# 08_C8051_TIMER_LCD_V1_0_0.net
KiCad netlist of a schematic drawn in Altium Designer
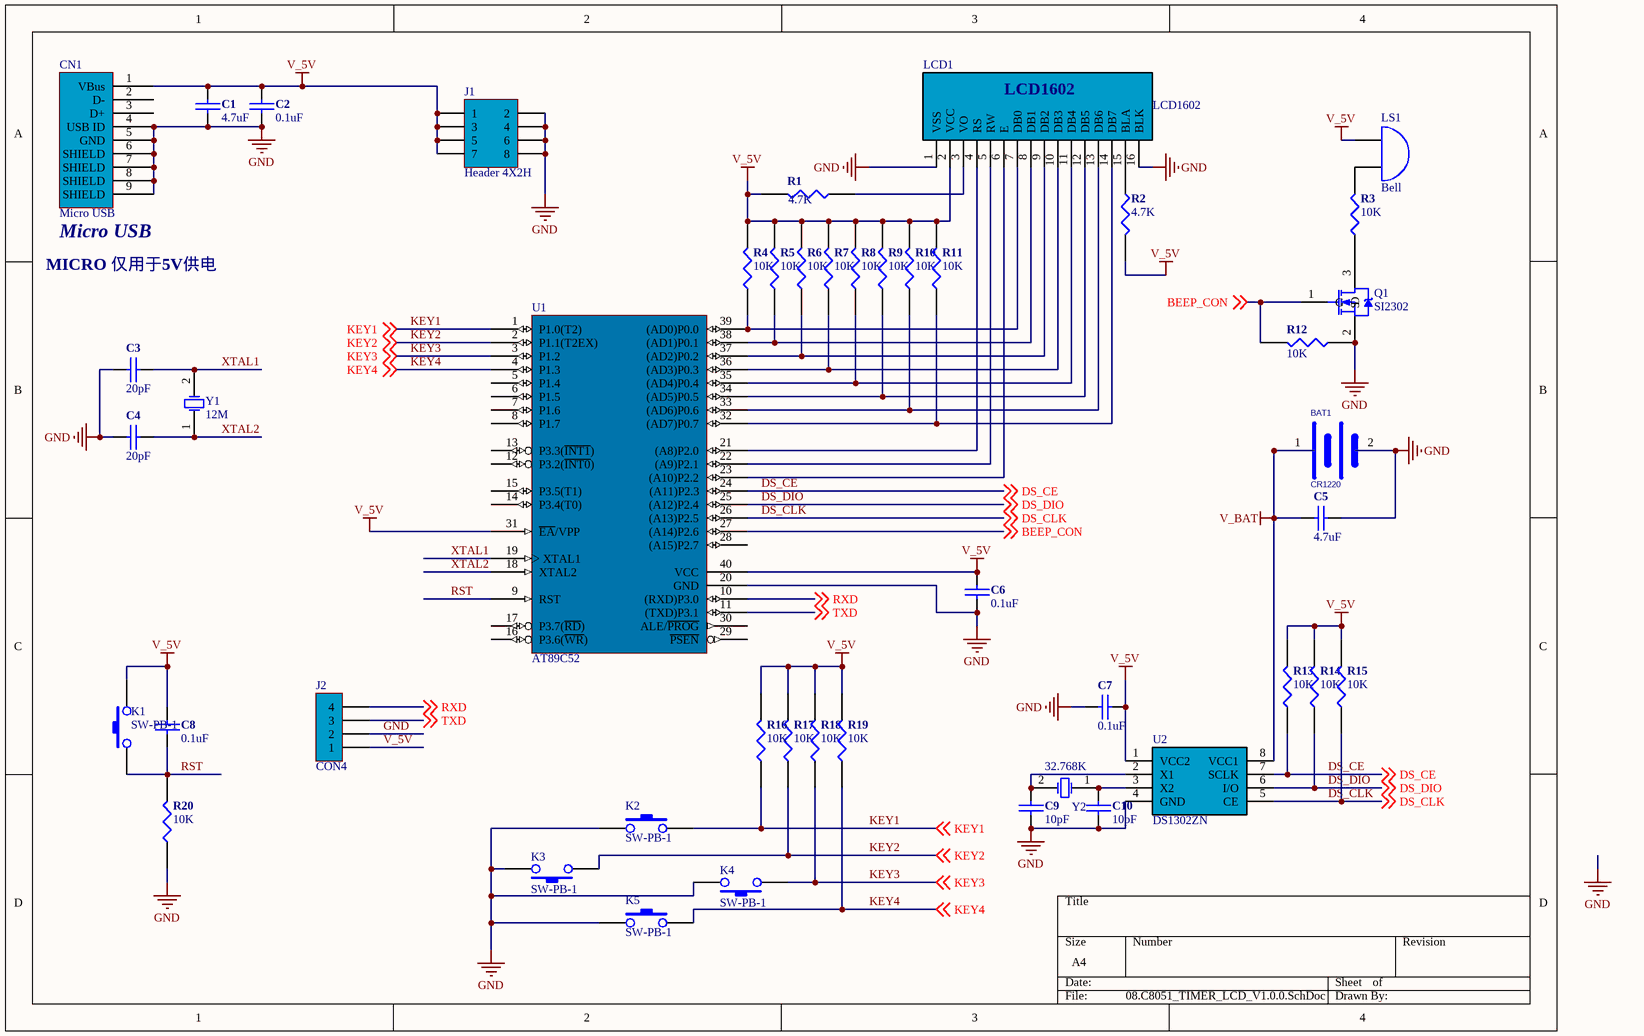
[diagram p0: 08.C8051_TIMER_LCD_V1.0.0.SchDoc]

(export (version "E")
  (design (tool "Eeschema 10.0.6"))
  (components
    (comp (ref "BAT1")
      (value "CR1220")
      (footprint "BATTERY-CELL")
      (libsource (lib "MyLibrarySum") (part "BATTERY"))
    )
    (comp (ref "C1")
      (value "4.7uF")
      (footprint "C0603")
      (description "SMT电容")
      (libsource (lib "") (part "CAP_1"))
    )
    (comp (ref "C2")
      (value "0.1uF")
      (footprint "C0603")
      (description "SMT电容")
      (libsource (lib "*") (part "电容"))
    )
    (comp (ref "C3")
      (value "20pF")
      (footprint "C0603")
      (description "SMT电容")
      (libsource (lib "*") (part "CAP"))
    )
    (comp (ref "C4")
      (value "20pF")
      (footprint "C0603")
      (description "SMT电容")
      (libsource (lib "*") (part "CAP"))
    )
    (comp (ref "C5")
      (value "4.7uF")
      (footprint "C0603")
      (description "SMT电容")
      (libsource (lib "*") (part "CAP"))
    )
    (comp (ref "C6")
      (value "0.1uF")
      (footprint "C0603")
      (description "SMT电容")
      (libsource (lib "*") (part "电容"))
    )
    (comp (ref "C7")
      (value "0.1uF")
      (footprint "C0603")
      (description "SMT电容")
      (libsource (lib "*") (part "电容"))
    )
    (comp (ref "C8")
      (value "0.1uF")
      (footprint "C0603")
      (description "SMT电容")
      (libsource (lib "*") (part "电容"))
    )
    (comp (ref "C9")
      (value "10pF")
      (footprint "C0603")
      (description "SMT电容")
      (libsource (lib "") (part "CAP_1"))
    )
    (comp (ref "C10")
      (value "10pF")
      (footprint "C0603")
      (description "SMT电容")
      (libsource (lib "") (part "CAP_1"))
    )
    (comp (ref "CN1")
      (value "Micro USB")
      (footprint "MICRO_USB_9")
      (description "Micro USB头")
      (fields (field (name "USAGE") "Micro USB"))
      (libsource (lib "MyLibrarySum") (part "Mini_USB_3"))
    )
    (comp (ref "J1")
      (value "Header 4X2H")
      (footprint "HDR2X4")
      (description "Header, 4-Pin, Dual row, Right Angle")
      (fields (field (name "PUBLISHER") "Altium Limited"))
      (libsource (lib "MyLibrarySum") (part "Header 4X2H"))
    )
    (comp (ref "J2")
      (value "CON4")
      (footprint "HDR1X4")
      (description "Connector")
      (libsource (lib "MyLibrarySum") (part "CON4"))
    )
    (comp (ref "K1")
      (value "SW-PB-1")
      (footprint "SWITCH_1")
      (description "轻触按键")
      (libsource (lib "HDZBLIB") (part "SW-PB-1"))
    )
    (comp (ref "K2")
      (value "SW-PB-1")
      (footprint "SWITCH_1")
      (description "轻触按键")
      (libsource (lib "HDZBLIB") (part "SW-PB-1"))
    )
    (comp (ref "K3")
      (value "SW-PB-1")
      (footprint "SWITCH_1")
      (description "轻触按键")
      (libsource (lib "HDZBLIB") (part "SW-PB-1"))
    )
    (comp (ref "K4")
      (value "SW-PB-1")
      (footprint "SWITCH_1")
      (description "轻触按键")
      (libsource (lib "HDZBLIB") (part "SW-PB-1"))
    )
    (comp (ref "K5")
      (value "SW-PB-1")
      (footprint "SWITCH_1")
      (description "轻触按键")
      (libsource (lib "HDZBLIB") (part "SW-PB-1"))
    )
    (comp (ref "LCD1")
      (value "LCD1602")
      (footprint "LCD1602")
      (libsource (lib "MyLibrarySum") (part "LCD1602"))
    )
    (comp (ref "LS1")
      (value "Bell")
      (footprint "BUZZER")
      (description "Electrical Bell")
      (fields (field (name "PUBLISHER") "Altium Limited"))
      (libsource (lib "MyLibrarySum") (part "Bell"))
    )
    (comp (ref "Q1")
      (value "SI2302")
      (footprint "SOT_23(N)")
      (description "N-Channel Power MOSFET")
      (fields (field (name "PUBLISHER") "Altium Limited"))
      (libsource (lib "MyLibrarySum") (part "NMOS-2"))
    )
    (comp (ref "R1")
      (value "4.7K")
      (footprint "R0603")
      (description "SMT电阻")
      (libsource (lib "*") (part "RES1"))
    )
    (comp (ref "R2")
      (value "4.7K")
      (footprint "R0603")
      (description "SMT电阻")
      (libsource (lib "*") (part "RES1"))
    )
    (comp (ref "R3")
      (value "10K")
      (footprint "R0603")
      (description "SMT电阻")
      (libsource (lib "*") (part "RES1"))
    )
    (comp (ref "R4")
      (value "10K")
      (footprint "R0603")
      (description "SMT电阻")
      (libsource (lib "*") (part "RES1"))
    )
    (comp (ref "R5")
      (value "10K")
      (footprint "R0603")
      (description "SMT电阻")
      (libsource (lib "*") (part "RES1"))
    )
    (comp (ref "R6")
      (value "10K")
      (footprint "R0603")
      (description "SMT电阻")
      (libsource (lib "*") (part "RES1"))
    )
    (comp (ref "R7")
      (value "10K")
      (footprint "R0603")
      (description "SMT电阻")
      (libsource (lib "*") (part "RES1"))
    )
    (comp (ref "R8")
      (value "10K")
      (footprint "R0603")
      (description "SMT电阻")
      (libsource (lib "*") (part "RES1"))
    )
    (comp (ref "R9")
      (value "10K")
      (footprint "R0603")
      (description "SMT电阻")
      (libsource (lib "*") (part "RES1"))
    )
    (comp (ref "R10")
      (value "10K")
      (footprint "R0603")
      (description "SMT电阻")
      (libsource (lib "*") (part "RES1"))
    )
    (comp (ref "R11")
      (value "10K")
      (footprint "R0603")
      (description "SMT电阻")
      (libsource (lib "*") (part "RES1"))
    )
    (comp (ref "R12")
      (value "10K")
      (footprint "R0603")
      (description "SMT电阻")
      (libsource (lib "*") (part "RES1"))
    )
    (comp (ref "R13")
      (value "10K")
      (footprint "R0603")
      (description "SMT电阻")
      (libsource (lib "*") (part "RES1"))
    )
    (comp (ref "R14")
      (value "10K")
      (footprint "R0603")
      (description "SMT电阻")
      (libsource (lib "*") (part "RES1"))
    )
    (comp (ref "R15")
      (value "10K")
      (footprint "R0603")
      (description "SMT电阻")
      (libsource (lib "*") (part "RES1"))
    )
    (comp (ref "R16")
      (value "10K")
      (footprint "R0603")
      (description "SMT电阻")
      (libsource (lib "*") (part "RES1"))
    )
    (comp (ref "R17")
      (value "10K")
      (footprint "R0603")
      (description "SMT电阻")
      (libsource (lib "*") (part "RES1"))
    )
    (comp (ref "R18")
      (value "10K")
      (footprint "R0603")
      (description "SMT电阻")
      (libsource (lib "*") (part "RES1"))
    )
    (comp (ref "R19")
      (value "10K")
      (footprint "R0603")
      (description "SMT电阻")
      (libsource (lib "*") (part "RES1"))
    )
    (comp (ref "R20")
      (value "10K")
      (footprint "R0603")
      (description "SMT电阻")
      (libsource (lib "*") (part "RES1"))
    )
    (comp (ref "U1")
      (value "AT89C52")
      (footprint "DIP40")
      (description "8-Bit Microcontroller with 8K Flash ROM")
      (libsource (lib "MyLibrarySum") (part "AT89C52"))
    )
    (comp (ref "U2") (value "DS1302ZN") (footprint "SOP-8") (libsource (lib "MyLibrarySum") (part "DS1302")))
    (comp (ref "Y1")
      (value "12M")
      (footprint "XTAL")
      (description "Crystal Oscillator")
      (fields (field (name "PUBLISHER") "Altium Limited"))
      (libsource (lib "MyLibrarySum") (part "XTAL"))
    )
    (comp (ref "Y2")
      (value "32.768K")
      (footprint "XTAL_32.768KHz")
      (description "Crystal Oscillator")
      (fields (field (name "PUBLISHER") "Altium Limited"))
      (libsource (lib "MyLibrarySum") (part "XTAL"))
    )
  )
  (nets
    (net (code "1") (name "/RST") (class "Default")
      (node (ref "C8") (pin "2") (pintype "passive"))
      (node (ref "K1") (pin "1") (pinfunction "1_1") (pintype "passive"))
      (node (ref "R20") (pin "2") (pinfunction "2_2") (pintype "passive"))
      (node (ref "U1") (pin "9") (pinfunction "RST_9") (pintype "input"))
    )
    (net (code "2") (name "/XTAL1") (class "Default")
      (node (ref "C3") (pin "1") (pinfunction "1_1") (pintype "passive"))
      (node (ref "U1") (pin "19") (pinfunction "XTAL1_19") (pintype "input"))
      (node (ref "Y1") (pin "2") (pinfunction "OSC2_2") (pintype "passive"))
    )
    (net (code "3") (name "/XTAL2") (class "Default")
      (node (ref "C4") (pin "1") (pinfunction "1_1") (pintype "passive"))
      (node (ref "U1") (pin "18") (pinfunction "XTAL2_18") (pintype "input"))
      (node (ref "Y1") (pin "1") (pinfunction "OSC1_1") (pintype "passive"))
    )
    (net (code "4") (name "BEEP_CON") (class "Default")
      (node (ref "Q1") (pin "1") (pinfunction "G_1") (pintype "passive"))
      (node (ref "R12") (pin "2") (pinfunction "2_2") (pintype "passive"))
      (node (ref "U1") (pin "27") (pinfunction "(A14)P2.6_27") (pintype "bidirectional"))
    )
    (net (code "5") (name "DS_CE") (class "Default")
      (node (ref "R13") (pin "1") (pinfunction "1_1") (pintype "passive"))
      (node (ref "U1") (pin "24") (pinfunction "(A11)P2.3_24") (pintype "bidirectional"))
      (node (ref "U2") (pin "7") (pinfunction "SCLK_7") (pintype "passive"))
    )
    (net (code "6") (name "DS_CLK") (class "Default")
      (node (ref "R15") (pin "1") (pinfunction "1_1") (pintype "passive"))
      (node (ref "U1") (pin "26") (pinfunction "(A13)P2.5_26") (pintype "bidirectional"))
      (node (ref "U2") (pin "5") (pinfunction "CE_5") (pintype "passive"))
    )
    (net (code "7") (name "DS_DIO") (class "Default")
      (node (ref "R14") (pin "1") (pinfunction "1_1") (pintype "passive"))
      (node (ref "U1") (pin "25") (pinfunction "(A12)P2.4_25") (pintype "bidirectional"))
      (node (ref "U2") (pin "6") (pinfunction "I/O_6") (pintype "passive"))
    )
    (net (code "8") (name "GND") (class "Default")
      (node (ref "BAT1") (pin "2") (pinfunction "GND_2") (pintype "passive"))
      (node (ref "C1") (pin "1") (pinfunction "1_1") (pintype "passive"))
      (node (ref "C10") (pin "2") (pinfunction "2_2") (pintype "passive"))
      (node (ref "C2") (pin "2") (pintype "passive"))
      (node (ref "C3") (pin "2") (pinfunction "2_2") (pintype "passive"))
      (node (ref "C4") (pin "2") (pinfunction "2_2") (pintype "passive"))
      (node (ref "C5") (pin "1") (pinfunction "1_1") (pintype "passive"))
      (node (ref "C6") (pin "2") (pintype "passive"))
      (node (ref "C7") (pin "1") (pintype "passive"))
      (node (ref "C9") (pin "2") (pinfunction "2_2") (pintype "passive"))
      (node (ref "CN1") (pin "4") (pinfunction "USB_ID_4") (pintype "passive"))
      (node (ref "CN1") (pin "5") (pinfunction "GND_5") (pintype "passive"))
      (node (ref "CN1") (pin "6") (pinfunction "SHIELD_6") (pintype "passive"))
      (node (ref "CN1") (pin "7") (pinfunction "SHIELD_7") (pintype "passive"))
      (node (ref "CN1") (pin "8") (pinfunction "SHIELD_8") (pintype "passive"))
      (node (ref "CN1") (pin "9") (pinfunction "SHIELD_9") (pintype "passive"))
      (node (ref "J1") (pin "2") (pinfunction "2_2") (pintype "passive"))
      (node (ref "J1") (pin "4") (pinfunction "4_4") (pintype "passive"))
      (node (ref "J1") (pin "6") (pinfunction "6_6") (pintype "passive"))
      (node (ref "J1") (pin "8") (pinfunction "8_8") (pintype "passive"))
      (node (ref "J2") (pin "2") (pinfunction "2_2") (pintype "passive"))
      (node (ref "K2") (pin "1") (pinfunction "1_1") (pintype "passive"))
      (node (ref "K3") (pin "2") (pinfunction "2_2") (pintype "passive"))
      (node (ref "K4") (pin "2") (pinfunction "2_2") (pintype "passive"))
      (node (ref "K5") (pin "1") (pinfunction "1_1") (pintype "passive"))
      (node (ref "LCD1") (pin "1") (pinfunction "VSS_1") (pintype "passive"))
      (node (ref "LCD1") (pin "16") (pinfunction "BLK_16") (pintype "passive"))
      (node (ref "Q1") (pin "2") (pinfunction "S_2") (pintype "passive"))
      (node (ref "R12") (pin "1") (pinfunction "1_1") (pintype "passive"))
      (node (ref "R20") (pin "1") (pinfunction "1_1") (pintype "passive"))
      (node (ref "U1") (pin "20") (pinfunction "GND_20") (pintype "power_in"))
      (node (ref "U2") (pin "4") (pinfunction "GND_4") (pintype "passive"))
    )
    (net (code "9") (name "KEY1") (class "Default")
      (node (ref "K2") (pin "2") (pinfunction "2_2") (pintype "passive"))
      (node (ref "R16") (pin "1") (pinfunction "1_1") (pintype "passive"))
      (node (ref "U1") (pin "1") (pinfunction "P1.0(T2)_1") (pintype "bidirectional"))
    )
    (net (code "10") (name "KEY2") (class "Default")
      (node (ref "K3") (pin "1") (pinfunction "1_1") (pintype "passive"))
      (node (ref "R17") (pin "1") (pinfunction "1_1") (pintype "passive"))
      (node (ref "U1") (pin "2") (pinfunction "P1.1(T2EX)_2") (pintype "bidirectional"))
    )
    (net (code "11") (name "KEY3") (class "Default")
      (node (ref "K4") (pin "1") (pinfunction "1_1") (pintype "passive"))
      (node (ref "R18") (pin "1") (pinfunction "1_1") (pintype "passive"))
      (node (ref "U1") (pin "3") (pinfunction "P1.2_3") (pintype "bidirectional"))
    )
    (net (code "12") (name "KEY4") (class "Default")
      (node (ref "K5") (pin "2") (pinfunction "2_2") (pintype "passive"))
      (node (ref "R19") (pin "1") (pinfunction "1_1") (pintype "passive"))
      (node (ref "U1") (pin "4") (pinfunction "P1.3_4") (pintype "bidirectional"))
    )
    (net (code "13") (name "Net-(LCD1-BLA)") (class "Default")
      (node (ref "LCD1") (pin "15") (pinfunction "BLA_15") (pintype "passive"))
      (node (ref "R2") (pin "1") (pinfunction "1_1") (pintype "passive"))
    )
    (net (code "14") (name "Net-(LCD1-DB0)") (class "Default")
      (node (ref "LCD1") (pin "7") (pinfunction "DB0_7") (pintype "passive"))
      (node (ref "R4") (pin "1") (pinfunction "1_1") (pintype "passive"))
      (node (ref "U1") (pin "39") (pinfunction "(AD0)P0.0_39") (pintype "bidirectional"))
    )
    (net (code "15") (name "Net-(LCD1-DB1)") (class "Default")
      (node (ref "LCD1") (pin "8") (pinfunction "DB1_8") (pintype "passive"))
      (node (ref "R5") (pin "1") (pinfunction "1_1") (pintype "passive"))
      (node (ref "U1") (pin "38") (pinfunction "(AD1)P0.1_38") (pintype "bidirectional"))
    )
    (net (code "16") (name "Net-(LCD1-DB2)") (class "Default")
      (node (ref "LCD1") (pin "9") (pinfunction "DB2_9") (pintype "passive"))
      (node (ref "R6") (pin "1") (pinfunction "1_1") (pintype "passive"))
      (node (ref "U1") (pin "37") (pinfunction "(AD2)P0.2_37") (pintype "bidirectional"))
    )
    (net (code "17") (name "Net-(LCD1-DB3)") (class "Default")
      (node (ref "LCD1") (pin "10") (pinfunction "DB3_10") (pintype "passive"))
      (node (ref "R7") (pin "1") (pinfunction "1_1") (pintype "passive"))
      (node (ref "U1") (pin "36") (pinfunction "(AD3)P0.3_36") (pintype "bidirectional"))
    )
    (net (code "18") (name "Net-(LCD1-DB4)") (class "Default")
      (node (ref "LCD1") (pin "11") (pinfunction "DB4_11") (pintype "passive"))
      (node (ref "R8") (pin "1") (pinfunction "1_1") (pintype "passive"))
      (node (ref "U1") (pin "35") (pinfunction "(AD4)P0.4_35") (pintype "bidirectional"))
    )
    (net (code "19") (name "Net-(LCD1-DB5)") (class "Default")
      (node (ref "LCD1") (pin "12") (pinfunction "DB5_12") (pintype "passive"))
      (node (ref "R9") (pin "1") (pinfunction "1_1") (pintype "passive"))
      (node (ref "U1") (pin "34") (pinfunction "(AD5)P0.5_34") (pintype "bidirectional"))
    )
    (net (code "20") (name "Net-(LCD1-DB6)") (class "Default")
      (node (ref "LCD1") (pin "13") (pinfunction "DB6_13") (pintype "passive"))
      (node (ref "R10") (pin "1") (pinfunction "1_1") (pintype "passive"))
      (node (ref "U1") (pin "33") (pinfunction "(AD6)P0.6_33") (pintype "bidirectional"))
    )
    (net (code "21") (name "Net-(LCD1-DB7)") (class "Default")
      (node (ref "LCD1") (pin "14") (pinfunction "DB7_14") (pintype "passive"))
      (node (ref "R11") (pin "1") (pinfunction "1_1") (pintype "passive"))
      (node (ref "U1") (pin "32") (pinfunction "(AD7)P0.7_32") (pintype "bidirectional"))
    )
    (net (code "22") (name "Net-(LCD1-E)") (class "Default")
      (node (ref "LCD1") (pin "6") (pinfunction "E_6") (pintype "passive"))
      (node (ref "U1") (pin "23") (pinfunction "(A10)P2.2_23") (pintype "bidirectional"))
    )
    (net (code "23") (name "Net-(LCD1-RS)") (class "Default")
      (node (ref "LCD1") (pin "4") (pinfunction "RS_4") (pintype "passive"))
      (node (ref "U1") (pin "21") (pinfunction "(A8)P2.0_21") (pintype "bidirectional"))
    )
    (net (code "24") (name "Net-(LCD1-RW)") (class "Default")
      (node (ref "LCD1") (pin "5") (pinfunction "RW_5") (pintype "passive"))
      (node (ref "U1") (pin "22") (pinfunction "(A9)P2.1_22") (pintype "bidirectional"))
    )
    (net (code "25") (name "Net-(LCD1-VO)") (class "Default")
      (node (ref "LCD1") (pin "3") (pinfunction "VO_3") (pintype "passive"))
      (node (ref "R1") (pin "1") (pinfunction "1_1") (pintype "passive"))
    )
    (net (code "26") (name "Net-(LS1-B)") (class "Default")
      (node (ref "LS1") (pin "2") (pinfunction "B_2") (pintype "passive"))
      (node (ref "R3") (pin "2") (pinfunction "2_2") (pintype "passive"))
    )
    (net (code "27") (name "Net-(Q1-D)") (class "Default")
      (node (ref "Q1") (pin "3") (pinfunction "D_3") (pintype "passive"))
      (node (ref "R3") (pin "1") (pinfunction "1_1") (pintype "passive"))
    )
    (net (code "28") (name "Net-(U2-X1)") (class "Default")
      (node (ref "C9") (pin "1") (pinfunction "1_1") (pintype "passive"))
      (node (ref "U2") (pin "2") (pinfunction "X1_2") (pintype "passive"))
      (node (ref "Y2") (pin "2") (pinfunction "OSC2_2") (pintype "passive"))
    )
    (net (code "29") (name "Net-(U2-X2)") (class "Default")
      (node (ref "C10") (pin "1") (pinfunction "1_1") (pintype "passive"))
      (node (ref "U2") (pin "3") (pinfunction "X2_3") (pintype "passive"))
      (node (ref "Y2") (pin "1") (pinfunction "OSC1_1") (pintype "passive"))
    )
    (net (code "30") (name "RXD") (class "Default")
      (node (ref "J2") (pin "4") (pinfunction "4_4") (pintype "passive"))
      (node (ref "U1") (pin "10") (pinfunction "(RXD)P3.0_10") (pintype "bidirectional"))
    )
    (net (code "31") (name "TXD") (class "Default")
      (node (ref "J2") (pin "3") (pinfunction "3_3") (pintype "passive"))
      (node (ref "U1") (pin "11") (pinfunction "(TXD)P3.1_11") (pintype "bidirectional"))
    )
    (net (code "32") (name "V_5V") (class "Default")
      (node (ref "C1") (pin "2") (pinfunction "2_2") (pintype "passive"))
      (node (ref "C2") (pin "1") (pintype "passive"))
      (node (ref "C6") (pin "1") (pintype "passive"))
      (node (ref "C7") (pin "2") (pintype "passive"))
      (node (ref "C8") (pin "1") (pintype "passive"))
      (node (ref "CN1") (pin "1") (pinfunction "VBus_1") (pintype "passive"))
      (node (ref "J1") (pin "1") (pinfunction "1_1") (pintype "passive"))
      (node (ref "J1") (pin "3") (pinfunction "3_3") (pintype "passive"))
      (node (ref "J1") (pin "5") (pinfunction "5_5") (pintype "passive"))
      (node (ref "J1") (pin "7") (pinfunction "7_7") (pintype "passive"))
      (node (ref "J2") (pin "1") (pinfunction "1_1") (pintype "passive"))
      (node (ref "K1") (pin "2") (pinfunction "2_2") (pintype "passive"))
      (node (ref "LCD1") (pin "2") (pinfunction "VCC_2") (pintype "passive"))
      (node (ref "LS1") (pin "1") (pinfunction "A_1") (pintype "passive"))
      (node (ref "R1") (pin "2") (pinfunction "2_2") (pintype "passive"))
      (node (ref "R10") (pin "2") (pinfunction "2_2") (pintype "passive"))
      (node (ref "R11") (pin "2") (pinfunction "2_2") (pintype "passive"))
      (node (ref "R13") (pin "2") (pinfunction "2_2") (pintype "passive"))
      (node (ref "R14") (pin "2") (pinfunction "2_2") (pintype "passive"))
      (node (ref "R15") (pin "2") (pinfunction "2_2") (pintype "passive"))
      (node (ref "R16") (pin "2") (pinfunction "2_2") (pintype "passive"))
      (node (ref "R17") (pin "2") (pinfunction "2_2") (pintype "passive"))
      (node (ref "R18") (pin "2") (pinfunction "2_2") (pintype "passive"))
      (node (ref "R19") (pin "2") (pinfunction "2_2") (pintype "passive"))
      (node (ref "R2") (pin "2") (pinfunction "2_2") (pintype "passive"))
      (node (ref "R4") (pin "2") (pinfunction "2_2") (pintype "passive"))
      (node (ref "R5") (pin "2") (pinfunction "2_2") (pintype "passive"))
      (node (ref "R6") (pin "2") (pinfunction "2_2") (pintype "passive"))
      (node (ref "R7") (pin "2") (pinfunction "2_2") (pintype "passive"))
      (node (ref "R8") (pin "2") (pinfunction "2_2") (pintype "passive"))
      (node (ref "R9") (pin "2") (pinfunction "2_2") (pintype "passive"))
      (node (ref "U1") (pin "31") (pinfunction "~{EA}/VPP_31") (pintype "input"))
      (node (ref "U1") (pin "40") (pinfunction "VCC_40") (pintype "power_in"))
      (node (ref "U2") (pin "1") (pinfunction "VCC2_1") (pintype "passive"))
    )
    (net (code "33") (name "V_BAT") (class "Default")
      (node (ref "BAT1") (pin "1") (pinfunction "+_1") (pintype "passive"))
      (node (ref "C5") (pin "2") (pinfunction "2_2") (pintype "passive"))
      (node (ref "U2") (pin "8") (pinfunction "VCC1_8") (pintype "passive"))
    )
    (net (code "34") (name "unconnected-(CN1-D+-Pad3)") (class "Default")
      (node (ref "CN1") (pin "3") (pinfunction "D+_3") (pintype "passive"))
    )
    (net (code "35") (name "unconnected-(CN1-D--Pad2)") (class "Default")
      (node (ref "CN1") (pin "2") (pinfunction "D-_2") (pintype "passive"))
    )
    (net (code "36") (name "unconnected-(U1-(A15)P2.7-Pad28)") (class "Default")
      (node (ref "U1") (pin "28") (pinfunction "(A15)P2.7_28") (pintype "bidirectional"))
    )
    (net (code "37") (name "unconnected-(U1-ALE{slash}~{PROG}-Pad30)") (class "Default")
      (node (ref "U1") (pin "30") (pinfunction "ALE/~{PROG}_30") (pintype "output"))
    )
    (net (code "38") (name "unconnected-(U1-P1.4-Pad5)") (class "Default")
      (node (ref "U1") (pin "5") (pinfunction "P1.4_5") (pintype "bidirectional"))
    )
    (net (code "39") (name "unconnected-(U1-P1.5-Pad6)") (class "Default")
      (node (ref "U1") (pin "6") (pinfunction "P1.5_6") (pintype "bidirectional"))
    )
    (net (code "40") (name "unconnected-(U1-P1.6-Pad7)") (class "Default")
      (node (ref "U1") (pin "7") (pinfunction "P1.6_7") (pintype "bidirectional"))
    )
    (net (code "41") (name "unconnected-(U1-P1.7-Pad8)") (class "Default")
      (node (ref "U1") (pin "8") (pinfunction "P1.7_8") (pintype "bidirectional"))
    )
    (net (code "42") (name "unconnected-(U1-P3.2(~{INT0})-Pad12)") (class "Default")
      (node (ref "U1") (pin "12") (pinfunction "P3.2(~{INT0})_12") (pintype "bidirectional"))
    )
    (net (code "43") (name "unconnected-(U1-P3.3(~{INT1})-Pad13)") (class "Default")
      (node (ref "U1") (pin "13") (pinfunction "P3.3(~{INT1})_13") (pintype "bidirectional"))
    )
    (net (code "44") (name "unconnected-(U1-P3.4(T0)-Pad14)") (class "Default")
      (node (ref "U1") (pin "14") (pinfunction "P3.4(T0)_14") (pintype "bidirectional"))
    )
    (net (code "45") (name "unconnected-(U1-P3.5(T1)-Pad15)") (class "Default")
      (node (ref "U1") (pin "15") (pinfunction "P3.5(T1)_15") (pintype "bidirectional"))
    )
    (net (code "46") (name "unconnected-(U1-P3.6(~{WR})-Pad16)") (class "Default")
      (node (ref "U1") (pin "16") (pinfunction "P3.6(~{WR})_16") (pintype "bidirectional"))
    )
    (net (code "47") (name "unconnected-(U1-P3.7(~{RD})-Pad17)") (class "Default")
      (node (ref "U1") (pin "17") (pinfunction "P3.7(~{RD})_17") (pintype "bidirectional"))
    )
    (net (code "48") (name "unconnected-(U1-~{PSEN}-Pad29)") (class "Default")
      (node (ref "U1") (pin "29") (pinfunction "~{PSEN}_29") (pintype "output"))
    )
  )
)
